# pt100.net
KiCad netlist of a schematic drawn in Altium Designer
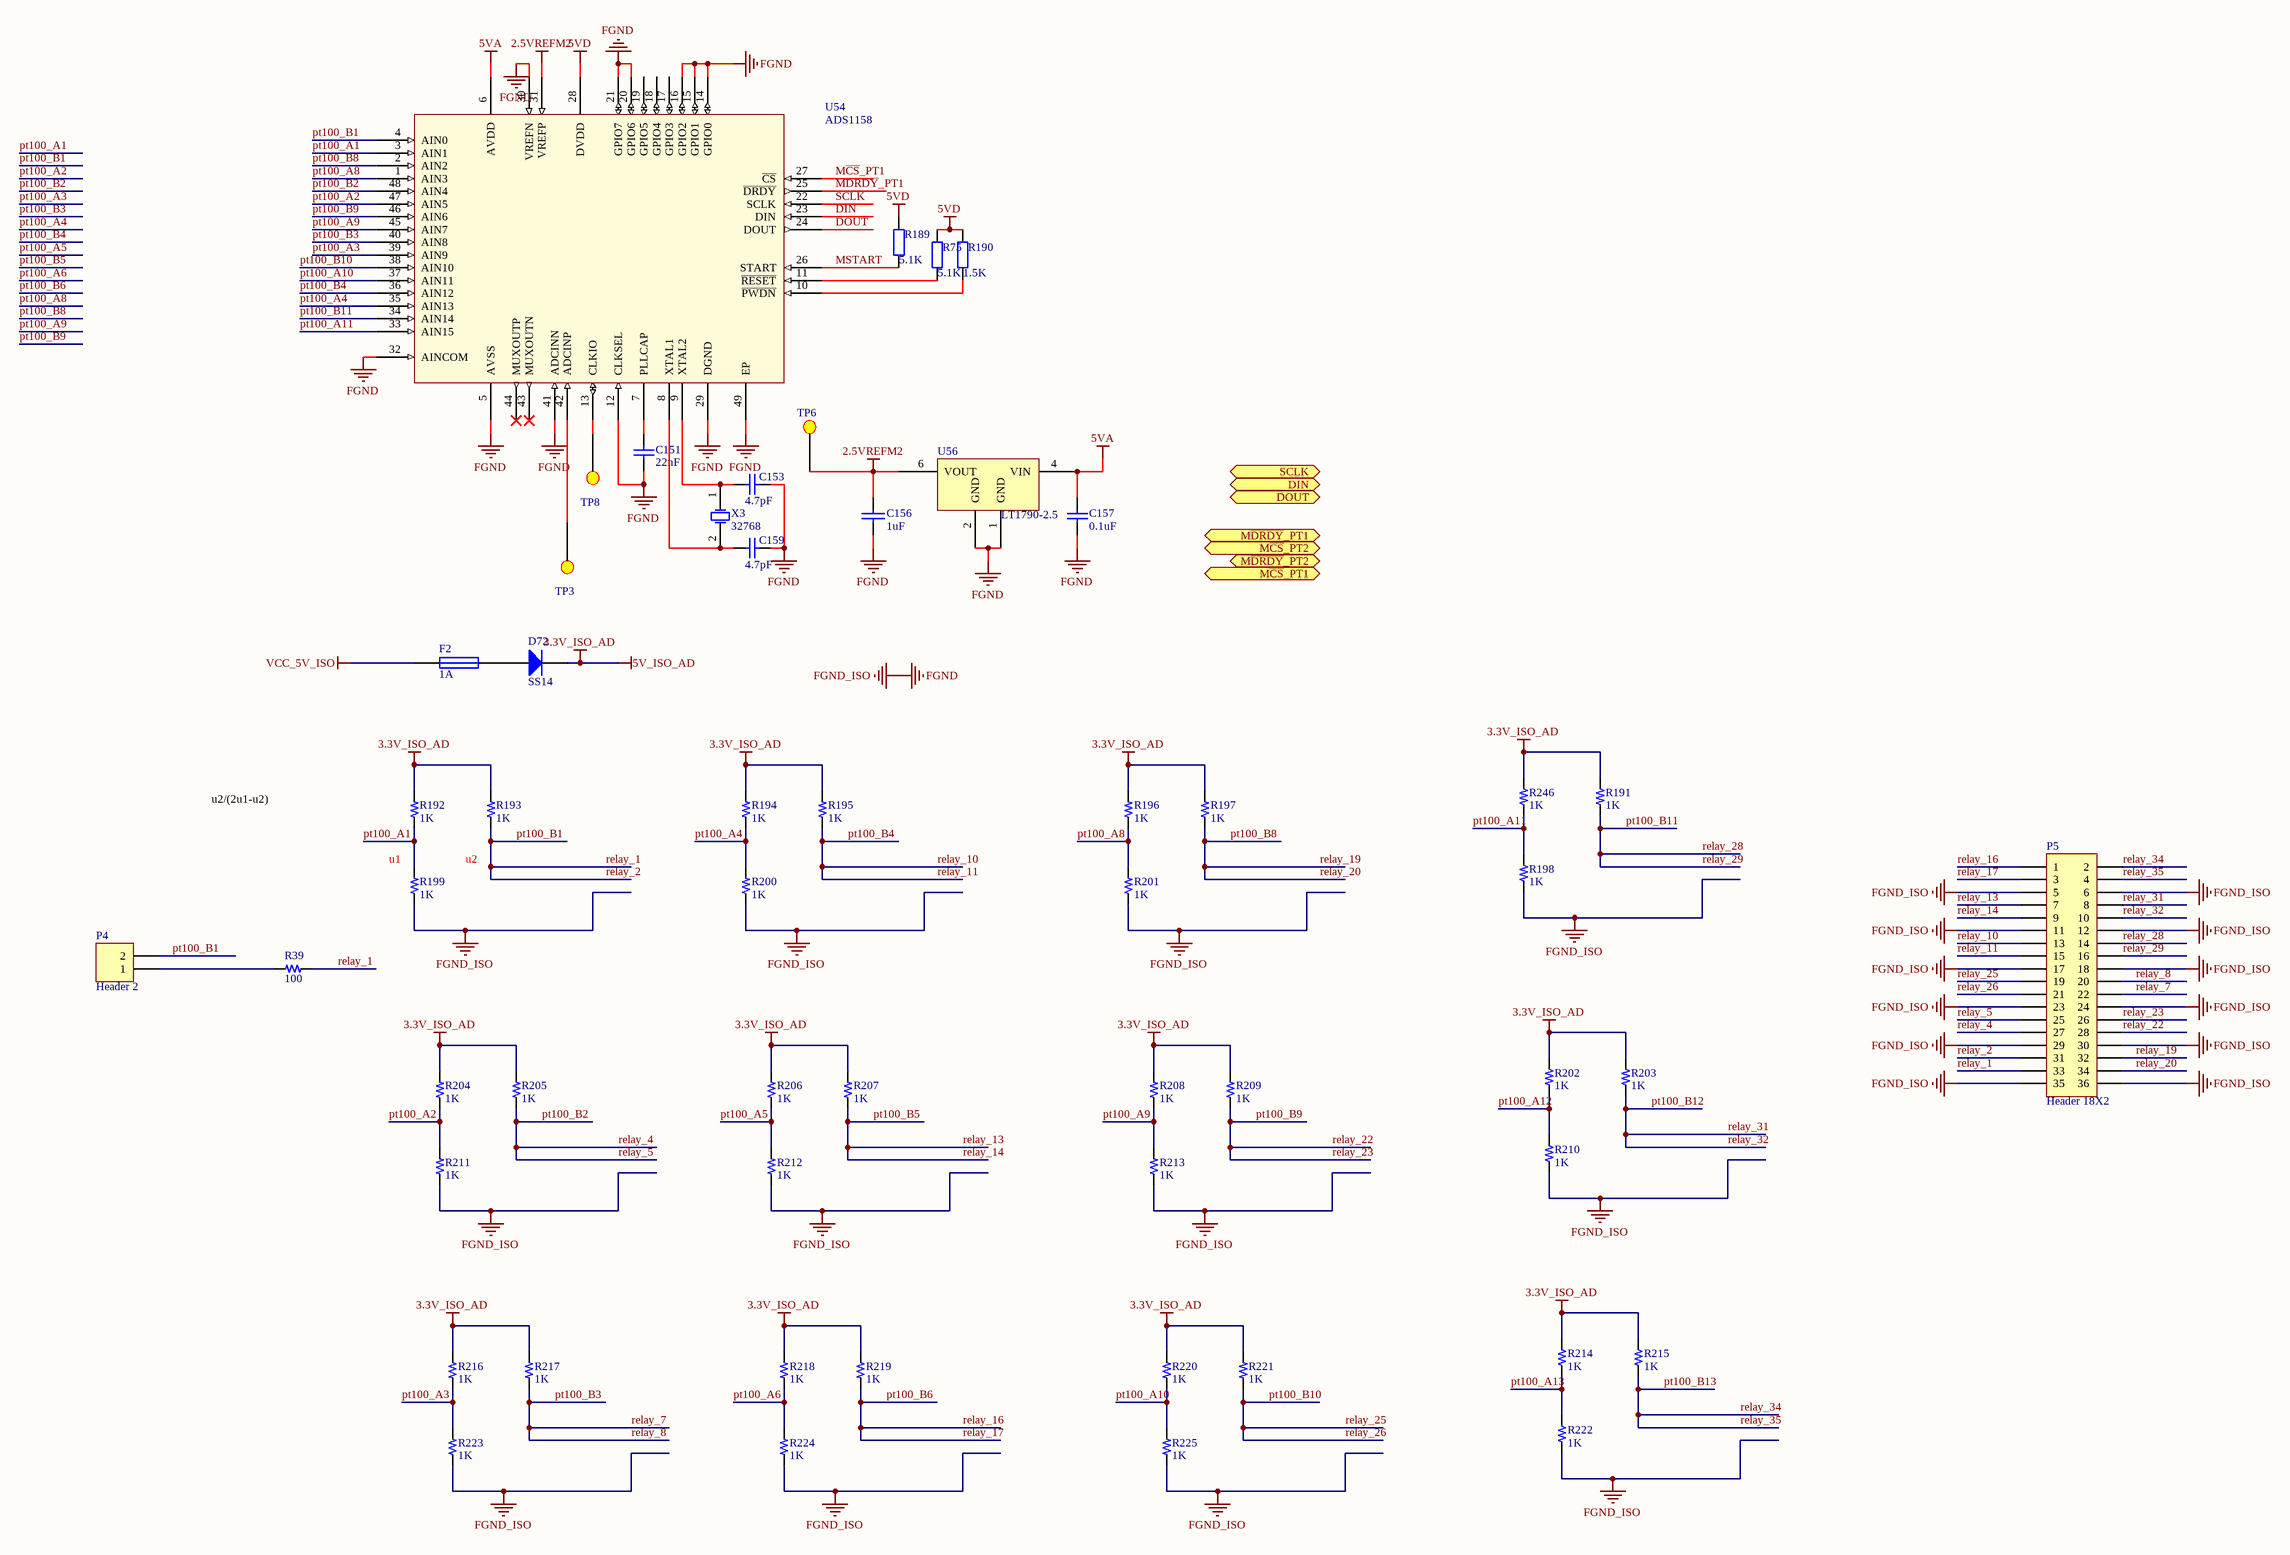
[diagram p0: pt100.SchDoc]

(export (version "E")
  (design (tool "Eeschema 10.0.6"))
  (components
    (comp (ref "C151")
      (value "22nF")
      (footprint "0805C")
      (description "Capacitor")
      (fields (field (name "PUBLISHER") "Altium Limited"))
      (libsource (lib "Miscellaneous Devices") (part "Cap"))
    )
    (comp (ref "C153")
      (value "4.7pF")
      (footprint "0603C")
      (description "Capacitor")
      (fields (field (name "PUBLISHER") "Altium Limited"))
      (libsource (lib "Miscellaneous Devices") (part "Cap"))
    )
    (comp (ref "C156")
      (value "1uF")
      (footprint "0603C")
      (description "Capacitor")
      (libsource (lib "*") (part "CAP"))
    )
    (comp (ref "C157")
      (value "0.1uF")
      (footprint "0603C")
      (description "Capacitor")
      (fields (field (name "PUBLISHER") "Altium Limited"))
      (libsource (lib "Miscellaneous Devices") (part "Cap"))
    )
    (comp (ref "C159")
      (value "4.7pF")
      (footprint "0603C")
      (description "Capacitor")
      (fields (field (name "PUBLISHER") "Altium Limited"))
      (libsource (lib "Miscellaneous Devices") (part "Cap"))
    )
    (comp (ref "D72")
      (value "SS14")
      (footprint "DO-214AC")
      (description "Default Diode")
      (fields (field (name "PUBLISHER") "Altium Limited"))
      (libsource (lib "Miscellaneous Devices") (part "Diode"))
    )
    (comp (ref "F2")
      (value "1A")
      (footprint "0805r")
      (description "Fuse")
      (fields (field (name "PUBLISHER") "Altium Limited"))
      (libsource (lib "Miscellaneous Devices") (part "Fuse 1"))
    )
    (comp (ref "P4")
      (value "Header 2")
      (footprint "HDR1X2")
      (description "Header, 2-Pin")
      (fields (field (name "PUBLISHER") "Altium Limited"))
      (libsource (lib "Miscellaneous Connectors") (part "Header 2"))
    )
    (comp (ref "P5")
      (value "Header 18X2")
      (footprint "XH2.54_2x18")
      (description "Header, 18-Pin, Dual row")
      (fields (field (name "PUBLISHER") "Altium Limited"))
      (libsource (lib "Miscellaneous Connectors") (part "Header 18X2"))
    )
    (comp (ref "R39")
      (value "100")
      (footprint "0603R")
      (description "R")
      (libsource (lib "JRJ_1") (part "R"))
    )
    (comp (ref "R75") (value "5.1K") (footprint "0603R") (libsource (lib "MQlibrary") (part "Res0805M")))
    (comp (ref "R189") (value "5.1K") (footprint "0603R") (libsource (lib "MQlibrary") (part "Res0805M")))
    (comp (ref "R190") (value "1.5K") (footprint "0603R") (libsource (lib "MQlibrary") (part "Res0805M")))
    (comp (ref "R191")
      (value "1K")
      (footprint "0603R")
      (description "R")
      (libsource (lib "JRJ_1") (part "R"))
    )
    (comp (ref "R192")
      (value "1K")
      (footprint "0603R")
      (description "R")
      (libsource (lib "JRJ_1") (part "R"))
    )
    (comp (ref "R193")
      (value "1K")
      (footprint "0603R")
      (description "R")
      (libsource (lib "JRJ_1") (part "R"))
    )
    (comp (ref "R194")
      (value "1K")
      (footprint "0603R")
      (description "R")
      (libsource (lib "JRJ_1") (part "R"))
    )
    (comp (ref "R195")
      (value "1K")
      (footprint "0603R")
      (description "R")
      (libsource (lib "JRJ_1") (part "R"))
    )
    (comp (ref "R196")
      (value "1K")
      (footprint "0603R")
      (description "R")
      (libsource (lib "JRJ_1") (part "R"))
    )
    (comp (ref "R197")
      (value "1K")
      (footprint "0603R")
      (description "R")
      (libsource (lib "JRJ_1") (part "R"))
    )
    (comp (ref "R198")
      (value "1K")
      (footprint "0603R")
      (description "R")
      (libsource (lib "JRJ_1") (part "R"))
    )
    (comp (ref "R199")
      (value "1K")
      (footprint "0603R")
      (description "R")
      (libsource (lib "JRJ_1") (part "R"))
    )
    (comp (ref "R200")
      (value "1K")
      (footprint "0603R")
      (description "R")
      (libsource (lib "JRJ_1") (part "R"))
    )
    (comp (ref "R201")
      (value "1K")
      (footprint "0603R")
      (description "R")
      (libsource (lib "JRJ_1") (part "R"))
    )
    (comp (ref "R202")
      (value "1K")
      (footprint "0603R")
      (description "R")
      (libsource (lib "JRJ_1") (part "R"))
    )
    (comp (ref "R203")
      (value "1K")
      (footprint "0603R")
      (description "R")
      (libsource (lib "JRJ_1") (part "R"))
    )
    (comp (ref "R204")
      (value "1K")
      (footprint "0603R")
      (description "R")
      (libsource (lib "JRJ_1") (part "R"))
    )
    (comp (ref "R205")
      (value "1K")
      (footprint "0603R")
      (description "R")
      (libsource (lib "JRJ_1") (part "R"))
    )
    (comp (ref "R206")
      (value "1K")
      (footprint "0603R")
      (description "R")
      (libsource (lib "JRJ_1") (part "R"))
    )
    (comp (ref "R207")
      (value "1K")
      (footprint "0603R")
      (description "R")
      (libsource (lib "JRJ_1") (part "R"))
    )
    (comp (ref "R208")
      (value "1K")
      (footprint "0603R")
      (description "R")
      (libsource (lib "JRJ_1") (part "R"))
    )
    (comp (ref "R209")
      (value "1K")
      (footprint "0603R")
      (description "R")
      (libsource (lib "JRJ_1") (part "R"))
    )
    (comp (ref "R210")
      (value "1K")
      (footprint "0603R")
      (description "R")
      (libsource (lib "JRJ_1") (part "R"))
    )
    (comp (ref "R211")
      (value "1K")
      (footprint "0603R")
      (description "R")
      (libsource (lib "JRJ_1") (part "R"))
    )
    (comp (ref "R212")
      (value "1K")
      (footprint "0603R")
      (description "R")
      (libsource (lib "JRJ_1") (part "R"))
    )
    (comp (ref "R213")
      (value "1K")
      (footprint "0603R")
      (description "R")
      (libsource (lib "JRJ_1") (part "R"))
    )
    (comp (ref "R214")
      (value "1K")
      (footprint "0603R")
      (description "R")
      (libsource (lib "JRJ_1") (part "R"))
    )
    (comp (ref "R215")
      (value "1K")
      (footprint "0603R")
      (description "R")
      (libsource (lib "JRJ_1") (part "R"))
    )
    (comp (ref "R216")
      (value "1K")
      (footprint "0603R")
      (description "R")
      (libsource (lib "JRJ_1") (part "R"))
    )
    (comp (ref "R217")
      (value "1K")
      (footprint "0603R")
      (description "R")
      (libsource (lib "JRJ_1") (part "R"))
    )
    (comp (ref "R218")
      (value "1K")
      (footprint "0603R")
      (description "R")
      (libsource (lib "JRJ_1") (part "R"))
    )
    (comp (ref "R219")
      (value "1K")
      (footprint "0603R")
      (description "R")
      (libsource (lib "JRJ_1") (part "R"))
    )
    (comp (ref "R220")
      (value "1K")
      (footprint "0603R")
      (description "R")
      (libsource (lib "JRJ_1") (part "R"))
    )
    (comp (ref "R221")
      (value "1K")
      (footprint "0603R")
      (description "R")
      (libsource (lib "JRJ_1") (part "R"))
    )
    (comp (ref "R222")
      (value "1K")
      (footprint "0603R")
      (description "R")
      (libsource (lib "JRJ_1") (part "R"))
    )
    (comp (ref "R223")
      (value "1K")
      (footprint "0603R")
      (description "R")
      (libsource (lib "JRJ_1") (part "R"))
    )
    (comp (ref "R224")
      (value "1K")
      (footprint "0603R")
      (description "R")
      (libsource (lib "JRJ_1") (part "R"))
    )
    (comp (ref "R225")
      (value "1K")
      (footprint "0603R")
      (description "R")
      (libsource (lib "JRJ_1") (part "R"))
    )
    (comp (ref "R246")
      (value "1K")
      (footprint "0603R")
      (description "R")
      (libsource (lib "JRJ_1") (part "R"))
    )
    (comp (ref "TP3")
      (value "TEST_POINT")
      (footprint "TPD")
      (libsource (lib "基带芯片OEM板_V1P0_张猛_20120921") (part "TEST_POINT"))
    )
    (comp (ref "TP6")
      (value "TEST_POINT")
      (footprint "TPD")
      (libsource (lib "基带芯片OEM板_V1P0_张猛_20120921") (part "TEST_POINT"))
    )
    (comp (ref "TP8")
      (value "TEST_POINT")
      (footprint "TPD")
      (libsource (lib "基带芯片OEM板_V1P0_张猛_20120921") (part "TEST_POINT"))
    )
    (comp (ref "U54")
      (value "ADS1158")
      (footprint "S-PVFQN-N48")
      (description "16-Channel, 16-Bit Analog-to-Digital Converter")
      (libsource (lib "Schlib") (part "ADS1158"))
    )
    (comp (ref "U56")
      (value "LT1790-2.5")
      (footprint "SOT23-6")
      (description "2.5V Micropower SOT-23  Low Dropout Reference")
      (libsource (lib "Schlib") (part "LT1790-2.5"))
    )
    (comp (ref "X3")
      (value "32768")
      (footprint "A")
      (description "Crystal Oscillator")
      (fields (field (name "PUBLISHER") "Altium Limited"))
      (libsource (lib "Miscellaneous Devices") (part "XTAL"))
    )
  )
  (nets
    (net (code "1") (name "/DIN") (class "Default")
      (node (ref "U54") (pin "23") (pinfunction "DIN_23") (pintype "input"))
    )
    (net (code "2") (name "/DOUT") (class "Default")
      (node (ref "U54") (pin "24") (pinfunction "DOUT_24") (pintype "output"))
    )
    (net (code "3") (name "/MSTART") (class "Default")
      (node (ref "R189") (pin "2") (pinfunction "2_2") (pintype "passive"))
      (node (ref "U54") (pin "26") (pinfunction "START_26") (pintype "input"))
    )
    (net (code "4") (name "/M~{CS}_PT1") (class "Default")
      (node (ref "U54") (pin "27") (pinfunction "~{CS}_27") (pintype "input"))
    )
    (net (code "6") (name "/M~{DRDY}_PT1") (class "Default")
      (node (ref "U54") (pin "25") (pinfunction "~{DRDY}_25") (pintype "output"))
    )
    (net (code "8") (name "/SCLK") (class "Default")
      (node (ref "U54") (pin "22") (pinfunction "SCLK_22") (pintype "input"))
    )
    (net (code "9") (name "/pt100_A1") (class "Default")
      (node (ref "R192") (pin "1") (pintype "passive"))
      (node (ref "R199") (pin "2") (pintype "passive"))
      (node (ref "U54") (pin "3") (pinfunction "AIN1_3") (pintype "input"))
    )
    (net (code "10") (name "/pt100_A2") (class "Default")
      (node (ref "R204") (pin "1") (pintype "passive"))
      (node (ref "R211") (pin "2") (pintype "passive"))
      (node (ref "U54") (pin "47") (pinfunction "AIN5_47") (pintype "input"))
    )
    (net (code "11") (name "/pt100_A3") (class "Default")
      (node (ref "R216") (pin "1") (pintype "passive"))
      (node (ref "R223") (pin "2") (pintype "passive"))
      (node (ref "U54") (pin "39") (pinfunction "AIN9_39") (pintype "input"))
    )
    (net (code "12") (name "/pt100_A4") (class "Default")
      (node (ref "R194") (pin "1") (pintype "passive"))
      (node (ref "R200") (pin "2") (pintype "passive"))
      (node (ref "U54") (pin "35") (pinfunction "AIN13_35") (pintype "input"))
    )
    (net (code "13") (name "/pt100_A5") (class "Default")
      (node (ref "R206") (pin "1") (pintype "passive"))
      (node (ref "R212") (pin "2") (pintype "passive"))
    )
    (net (code "14") (name "/pt100_A6") (class "Default")
      (node (ref "R218") (pin "1") (pintype "passive"))
      (node (ref "R224") (pin "2") (pintype "passive"))
    )
    (net (code "15") (name "/pt100_A8") (class "Default")
      (node (ref "R196") (pin "1") (pintype "passive"))
      (node (ref "R201") (pin "2") (pintype "passive"))
      (node (ref "U54") (pin "1") (pinfunction "AIN3_1") (pintype "input"))
    )
    (net (code "16") (name "/pt100_A9") (class "Default")
      (node (ref "R208") (pin "1") (pintype "passive"))
      (node (ref "R213") (pin "2") (pintype "passive"))
      (node (ref "U54") (pin "45") (pinfunction "AIN7_45") (pintype "input"))
    )
    (net (code "17") (name "/pt100_A10") (class "Default")
      (node (ref "R220") (pin "1") (pintype "passive"))
      (node (ref "R225") (pin "2") (pintype "passive"))
      (node (ref "U54") (pin "37") (pinfunction "AIN11_37") (pintype "input"))
    )
    (net (code "18") (name "/pt100_A11") (class "Default")
      (node (ref "R198") (pin "2") (pintype "passive"))
      (node (ref "R246") (pin "1") (pintype "passive"))
      (node (ref "U54") (pin "33") (pinfunction "AIN15_33") (pintype "input"))
    )
    (net (code "19") (name "/pt100_A12") (class "Default")
      (node (ref "R202") (pin "1") (pintype "passive"))
      (node (ref "R210") (pin "2") (pintype "passive"))
    )
    (net (code "20") (name "/pt100_A13") (class "Default")
      (node (ref "R214") (pin "1") (pintype "passive"))
      (node (ref "R222") (pin "2") (pintype "passive"))
    )
    (net (code "21") (name "/pt100_B1") (class "Default")
      (node (ref "P4") (pin "2") (pinfunction "2_2") (pintype "passive"))
      (node (ref "P5") (pin "31") (pinfunction "31_31") (pintype "passive"))
      (node (ref "P5") (pin "33") (pinfunction "33_33") (pintype "passive"))
      (node (ref "R193") (pin "1") (pintype "passive"))
      (node (ref "R39") (pin "1") (pintype "passive"))
      (node (ref "U54") (pin "4") (pinfunction "AIN0_4") (pintype "input"))
    )
    (net (code "22") (name "/pt100_B2") (class "Default")
      (node (ref "P5") (pin "25") (pinfunction "25_25") (pintype "passive"))
      (node (ref "P5") (pin "27") (pinfunction "27_27") (pintype "passive"))
      (node (ref "R205") (pin "1") (pintype "passive"))
      (node (ref "U54") (pin "48") (pinfunction "AIN4_48") (pintype "input"))
    )
    (net (code "23") (name "/pt100_B3") (class "Default")
      (node (ref "P5") (pin "20") (pinfunction "20_20") (pintype "passive"))
      (node (ref "P5") (pin "22") (pinfunction "22_22") (pintype "passive"))
      (node (ref "R217") (pin "1") (pintype "passive"))
      (node (ref "U54") (pin "40") (pinfunction "AIN8_40") (pintype "input"))
    )
    (net (code "24") (name "/pt100_B4") (class "Default")
      (node (ref "P5") (pin "13") (pinfunction "13_13") (pintype "passive"))
      (node (ref "P5") (pin "15") (pinfunction "15_15") (pintype "passive"))
      (node (ref "R195") (pin "1") (pintype "passive"))
      (node (ref "U54") (pin "36") (pinfunction "AIN12_36") (pintype "input"))
    )
    (net (code "25") (name "/pt100_B5") (class "Default")
      (node (ref "P5") (pin "7") (pinfunction "7_7") (pintype "passive"))
      (node (ref "P5") (pin "9") (pinfunction "9_9") (pintype "passive"))
      (node (ref "R207") (pin "1") (pintype "passive"))
    )
    (net (code "26") (name "/pt100_B6") (class "Default")
      (node (ref "P5") (pin "1") (pinfunction "1_1") (pintype "passive"))
      (node (ref "P5") (pin "3") (pinfunction "3_3") (pintype "passive"))
      (node (ref "R219") (pin "1") (pintype "passive"))
    )
    (net (code "27") (name "/pt100_B8") (class "Default")
      (node (ref "P5") (pin "32") (pinfunction "32_32") (pintype "passive"))
      (node (ref "P5") (pin "34") (pinfunction "34_34") (pintype "passive"))
      (node (ref "R197") (pin "1") (pintype "passive"))
      (node (ref "U54") (pin "2") (pinfunction "AIN2_2") (pintype "input"))
    )
    (net (code "28") (name "/pt100_B9") (class "Default")
      (node (ref "P5") (pin "26") (pinfunction "26_26") (pintype "passive"))
      (node (ref "P5") (pin "28") (pinfunction "28_28") (pintype "passive"))
      (node (ref "R209") (pin "1") (pintype "passive"))
      (node (ref "U54") (pin "46") (pinfunction "AIN6_46") (pintype "input"))
    )
    (net (code "29") (name "/pt100_B10") (class "Default")
      (node (ref "P5") (pin "19") (pinfunction "19_19") (pintype "passive"))
      (node (ref "P5") (pin "21") (pinfunction "21_21") (pintype "passive"))
      (node (ref "R221") (pin "1") (pintype "passive"))
      (node (ref "U54") (pin "38") (pinfunction "AIN10_38") (pintype "input"))
    )
    (net (code "30") (name "/pt100_B11") (class "Default")
      (node (ref "P5") (pin "14") (pinfunction "14_14") (pintype "passive"))
      (node (ref "P5") (pin "16") (pinfunction "16_16") (pintype "passive"))
      (node (ref "R191") (pin "1") (pintype "passive"))
      (node (ref "U54") (pin "34") (pinfunction "AIN14_34") (pintype "input"))
    )
    (net (code "31") (name "/pt100_B12") (class "Default")
      (node (ref "P5") (pin "10") (pinfunction "10_10") (pintype "passive"))
      (node (ref "P5") (pin "8") (pinfunction "8_8") (pintype "passive"))
      (node (ref "R203") (pin "1") (pintype "passive"))
    )
    (net (code "32") (name "/pt100_B13") (class "Default")
      (node (ref "P5") (pin "2") (pinfunction "2_2") (pintype "passive"))
      (node (ref "P5") (pin "4") (pinfunction "4_4") (pintype "passive"))
      (node (ref "R215") (pin "1") (pintype "passive"))
    )
    (net (code "33") (name "2.5VREFM2") (class "Default")
      (node (ref "C156") (pin "1") (pinfunction "1_1") (pintype "passive"))
      (node (ref "TP6") (pin "1") (pinfunction "1_1") (pintype "passive"))
      (node (ref "U54") (pin "31") (pinfunction "VREFP_31") (pintype "input"))
      (node (ref "U56") (pin "6") (pinfunction "VOUT_6") (pintype "power_in"))
    )
    (net (code "34") (name "3.3V_ISO_AD") (class "Default")
      (node (ref "D72") (pin "2") (pinfunction "K_2") (pintype "passive"))
      (node (ref "R191") (pin "2") (pintype "passive"))
      (node (ref "R192") (pin "2") (pintype "passive"))
      (node (ref "R193") (pin "2") (pintype "passive"))
      (node (ref "R194") (pin "2") (pintype "passive"))
      (node (ref "R195") (pin "2") (pintype "passive"))
      (node (ref "R196") (pin "2") (pintype "passive"))
      (node (ref "R197") (pin "2") (pintype "passive"))
      (node (ref "R202") (pin "2") (pintype "passive"))
      (node (ref "R203") (pin "2") (pintype "passive"))
      (node (ref "R204") (pin "2") (pintype "passive"))
      (node (ref "R205") (pin "2") (pintype "passive"))
      (node (ref "R206") (pin "2") (pintype "passive"))
      (node (ref "R207") (pin "2") (pintype "passive"))
      (node (ref "R208") (pin "2") (pintype "passive"))
      (node (ref "R209") (pin "2") (pintype "passive"))
      (node (ref "R214") (pin "2") (pintype "passive"))
      (node (ref "R215") (pin "2") (pintype "passive"))
      (node (ref "R216") (pin "2") (pintype "passive"))
      (node (ref "R217") (pin "2") (pintype "passive"))
      (node (ref "R218") (pin "2") (pintype "passive"))
      (node (ref "R219") (pin "2") (pintype "passive"))
      (node (ref "R220") (pin "2") (pintype "passive"))
      (node (ref "R221") (pin "2") (pintype "passive"))
      (node (ref "R246") (pin "2") (pintype "passive"))
    )
    (net (code "35") (name "5VA") (class "Default")
      (node (ref "C157") (pin "2") (pinfunction "2_2") (pintype "passive"))
      (node (ref "U54") (pin "6") (pinfunction "AVDD_6") (pintype "passive"))
      (node (ref "U56") (pin "4") (pinfunction "VIN_4") (pintype "power_in"))
    )
    (net (code "36") (name "5VD") (class "Default")
      (node (ref "R189") (pin "1") (pinfunction "1_1") (pintype "passive"))
      (node (ref "R190") (pin "1") (pinfunction "1_1") (pintype "passive"))
      (node (ref "R75") (pin "1") (pinfunction "1_1") (pintype "passive"))
      (node (ref "U54") (pin "28") (pinfunction "DVDD_28") (pintype "power_in"))
    )
    (net (code "37") (name "FGND") (class "Default")
      (node (ref "C151") (pin "2") (pinfunction "2_2") (pintype "passive"))
      (node (ref "C153") (pin "2") (pinfunction "2_2") (pintype "passive"))
      (node (ref "C156") (pin "2") (pinfunction "2_2") (pintype "passive"))
      (node (ref "C157") (pin "1") (pinfunction "1_1") (pintype "passive"))
      (node (ref "C159") (pin "2") (pinfunction "2_2") (pintype "passive"))
      (node (ref "P5") (pin "11") (pinfunction "11_11") (pintype "passive"))
      (node (ref "P5") (pin "12") (pinfunction "12_12") (pintype "passive"))
      (node (ref "P5") (pin "17") (pinfunction "17_17") (pintype "passive"))
      (node (ref "P5") (pin "18") (pinfunction "18_18") (pintype "passive"))
      (node (ref "P5") (pin "23") (pinfunction "23_23") (pintype "passive"))
      (node (ref "P5") (pin "24") (pinfunction "24_24") (pintype "passive"))
      (node (ref "P5") (pin "29") (pinfunction "29_29") (pintype "passive"))
      (node (ref "P5") (pin "30") (pinfunction "30_30") (pintype "passive"))
      (node (ref "P5") (pin "35") (pinfunction "35_35") (pintype "passive"))
      (node (ref "P5") (pin "36") (pinfunction "36_36") (pintype "passive"))
      (node (ref "P5") (pin "5") (pinfunction "5_5") (pintype "passive"))
      (node (ref "P5") (pin "6") (pinfunction "6_6") (pintype "passive"))
      (node (ref "R198") (pin "1") (pintype "passive"))
      (node (ref "R199") (pin "1") (pintype "passive"))
      (node (ref "R200") (pin "1") (pintype "passive"))
      (node (ref "R201") (pin "1") (pintype "passive"))
      (node (ref "R210") (pin "1") (pintype "passive"))
      (node (ref "R211") (pin "1") (pintype "passive"))
      (node (ref "R212") (pin "1") (pintype "passive"))
      (node (ref "R213") (pin "1") (pintype "passive"))
      (node (ref "R222") (pin "1") (pintype "passive"))
      (node (ref "R223") (pin "1") (pintype "passive"))
      (node (ref "R224") (pin "1") (pintype "passive"))
      (node (ref "R225") (pin "1") (pintype "passive"))
      (node (ref "U54") (pin "12") (pinfunction "CLKSEL_12") (pintype "input"))
      (node (ref "U54") (pin "14") (pinfunction "GPIO0_14") (pintype "bidirectional"))
      (node (ref "U54") (pin "15") (pinfunction "GPIO1_15") (pintype "bidirectional"))
      (node (ref "U54") (pin "16") (pinfunction "GPIO2_16") (pintype "bidirectional"))
      (node (ref "U54") (pin "20") (pinfunction "GPIO6_20") (pintype "bidirectional"))
      (node (ref "U54") (pin "21") (pinfunction "GPIO7_21") (pintype "bidirectional"))
      (node (ref "U54") (pin "29") (pinfunction "DGND_29") (pintype "power_in"))
      (node (ref "U54") (pin "30") (pinfunction "VREFN_30") (pintype "input"))
      (node (ref "U54") (pin "32") (pinfunction "AINCOM_32") (pintype "input"))
      (node (ref "U54") (pin "41") (pinfunction "ADCINN_41") (pintype "input"))
      (node (ref "U54") (pin "49") (pinfunction "EP_49") (pintype "passive"))
      (node (ref "U54") (pin "5") (pinfunction "AVSS_5") (pintype "power_in"))
      (node (ref "U56") (pin "1") (pinfunction "GND_1") (pintype "power_in"))
      (node (ref "U56") (pin "2") (pinfunction "GND_2") (pintype "power_in"))
    )
    (net (code "38") (name "Net-(D72-A)") (class "Default")
      (node (ref "D72") (pin "1") (pinfunction "A_1") (pintype "passive"))
      (node (ref "F2") (pin "2") (pinfunction "2_2") (pintype "passive"))
    )
    (net (code "39") (name "Net-(P4-Pad1)") (class "Default")
      (node (ref "P4") (pin "1") (pinfunction "1_1") (pintype "passive"))
      (node (ref "R39") (pin "2") (pintype "passive"))
    )
    (net (code "40") (name "Net-(U54-ADCINP)") (class "Default")
      (node (ref "TP3") (pin "1") (pinfunction "1_1") (pintype "passive"))
      (node (ref "U54") (pin "42") (pinfunction "ADCINP_42") (pintype "input"))
    )
    (net (code "41") (name "Net-(U54-CLKIO)") (class "Default")
      (node (ref "TP8") (pin "1") (pinfunction "1_1") (pintype "passive"))
      (node (ref "U54") (pin "13") (pinfunction "CLKIO_13") (pintype "bidirectional"))
    )
    (net (code "42") (name "Net-(U54-PLLCAP)") (class "Default")
      (node (ref "C151") (pin "1") (pinfunction "1_1") (pintype "passive"))
      (node (ref "U54") (pin "7") (pinfunction "PLLCAP_7") (pintype "power_in"))
    )
    (net (code "43") (name "Net-(U54-XTAL1)") (class "Default")
      (node (ref "C159") (pin "1") (pinfunction "1_1") (pintype "passive"))
      (node (ref "U54") (pin "8") (pinfunction "XTAL1_8") (pintype "passive"))
      (node (ref "X3") (pin "2") (pinfunction "OSC2_2") (pintype "passive"))
    )
    (net (code "44") (name "Net-(U54-XTAL2)") (class "Default")
      (node (ref "C153") (pin "1") (pinfunction "1_1") (pintype "passive"))
      (node (ref "U54") (pin "9") (pinfunction "XTAL2_9") (pintype "passive"))
      (node (ref "X3") (pin "1") (pinfunction "OSC1_1") (pintype "passive"))
    )
    (net (code "45") (name "Net-(U54-~{PWDN})") (class "Default")
      (node (ref "R190") (pin "2") (pinfunction "2_2") (pintype "passive"))
      (node (ref "U54") (pin "10") (pinfunction "~{PWDN}_10") (pintype "input"))
    )
    (net (code "46") (name "Net-(U54-~{RESET})") (class "Default")
      (node (ref "R75") (pin "2") (pinfunction "2_2") (pintype "passive"))
      (node (ref "U54") (pin "11") (pinfunction "~{RESET}_11") (pintype "input"))
    )
    (net (code "47") (name "VCC_5V_ISO") (class "Default")
      (node (ref "F2") (pin "1") (pinfunction "1_1") (pintype "passive"))
    )
    (net (code "48") (name "unconnected-(U54-GPIO3-Pad17)") (class "Default")
      (node (ref "U54") (pin "17") (pinfunction "GPIO3_17") (pintype "bidirectional"))
    )
    (net (code "49") (name "unconnected-(U54-GPIO4-Pad18)") (class "Default")
      (node (ref "U54") (pin "18") (pinfunction "GPIO4_18") (pintype "bidirectional"))
    )
    (net (code "50") (name "unconnected-(U54-GPIO5-Pad19)") (class "Default")
      (node (ref "U54") (pin "19") (pinfunction "GPIO5_19") (pintype "bidirectional"))
    )
    (net (code "51") (name "unconnected-(U54-MUXOUTN-Pad43)") (class "Default")
      (node (ref "U54") (pin "43") (pinfunction "MUXOUTN_43") (pintype "output+no_connect"))
    )
    (net (code "52") (name "unconnected-(U54-MUXOUTP-Pad44)") (class "Default")
      (node (ref "U54") (pin "44") (pinfunction "MUXOUTP_44") (pintype "output+no_connect"))
    )
    (net (code "53") (name "unconnected-(U56-DNC-Pad3)") (class "Default")
      (node (ref "U56") (pin "3") (pinfunction "DNC_3") (pintype "passive"))
    )
    (net (code "54") (name "unconnected-(U56-DNC-Pad5)") (class "Default")
      (node (ref "U56") (pin "5") (pinfunction "DNC_5") (pintype "passive"))
    )
  )
)
